# wagband_schematic_pre_route.net
KiCad netlist of a schematic drawn in EAGLE
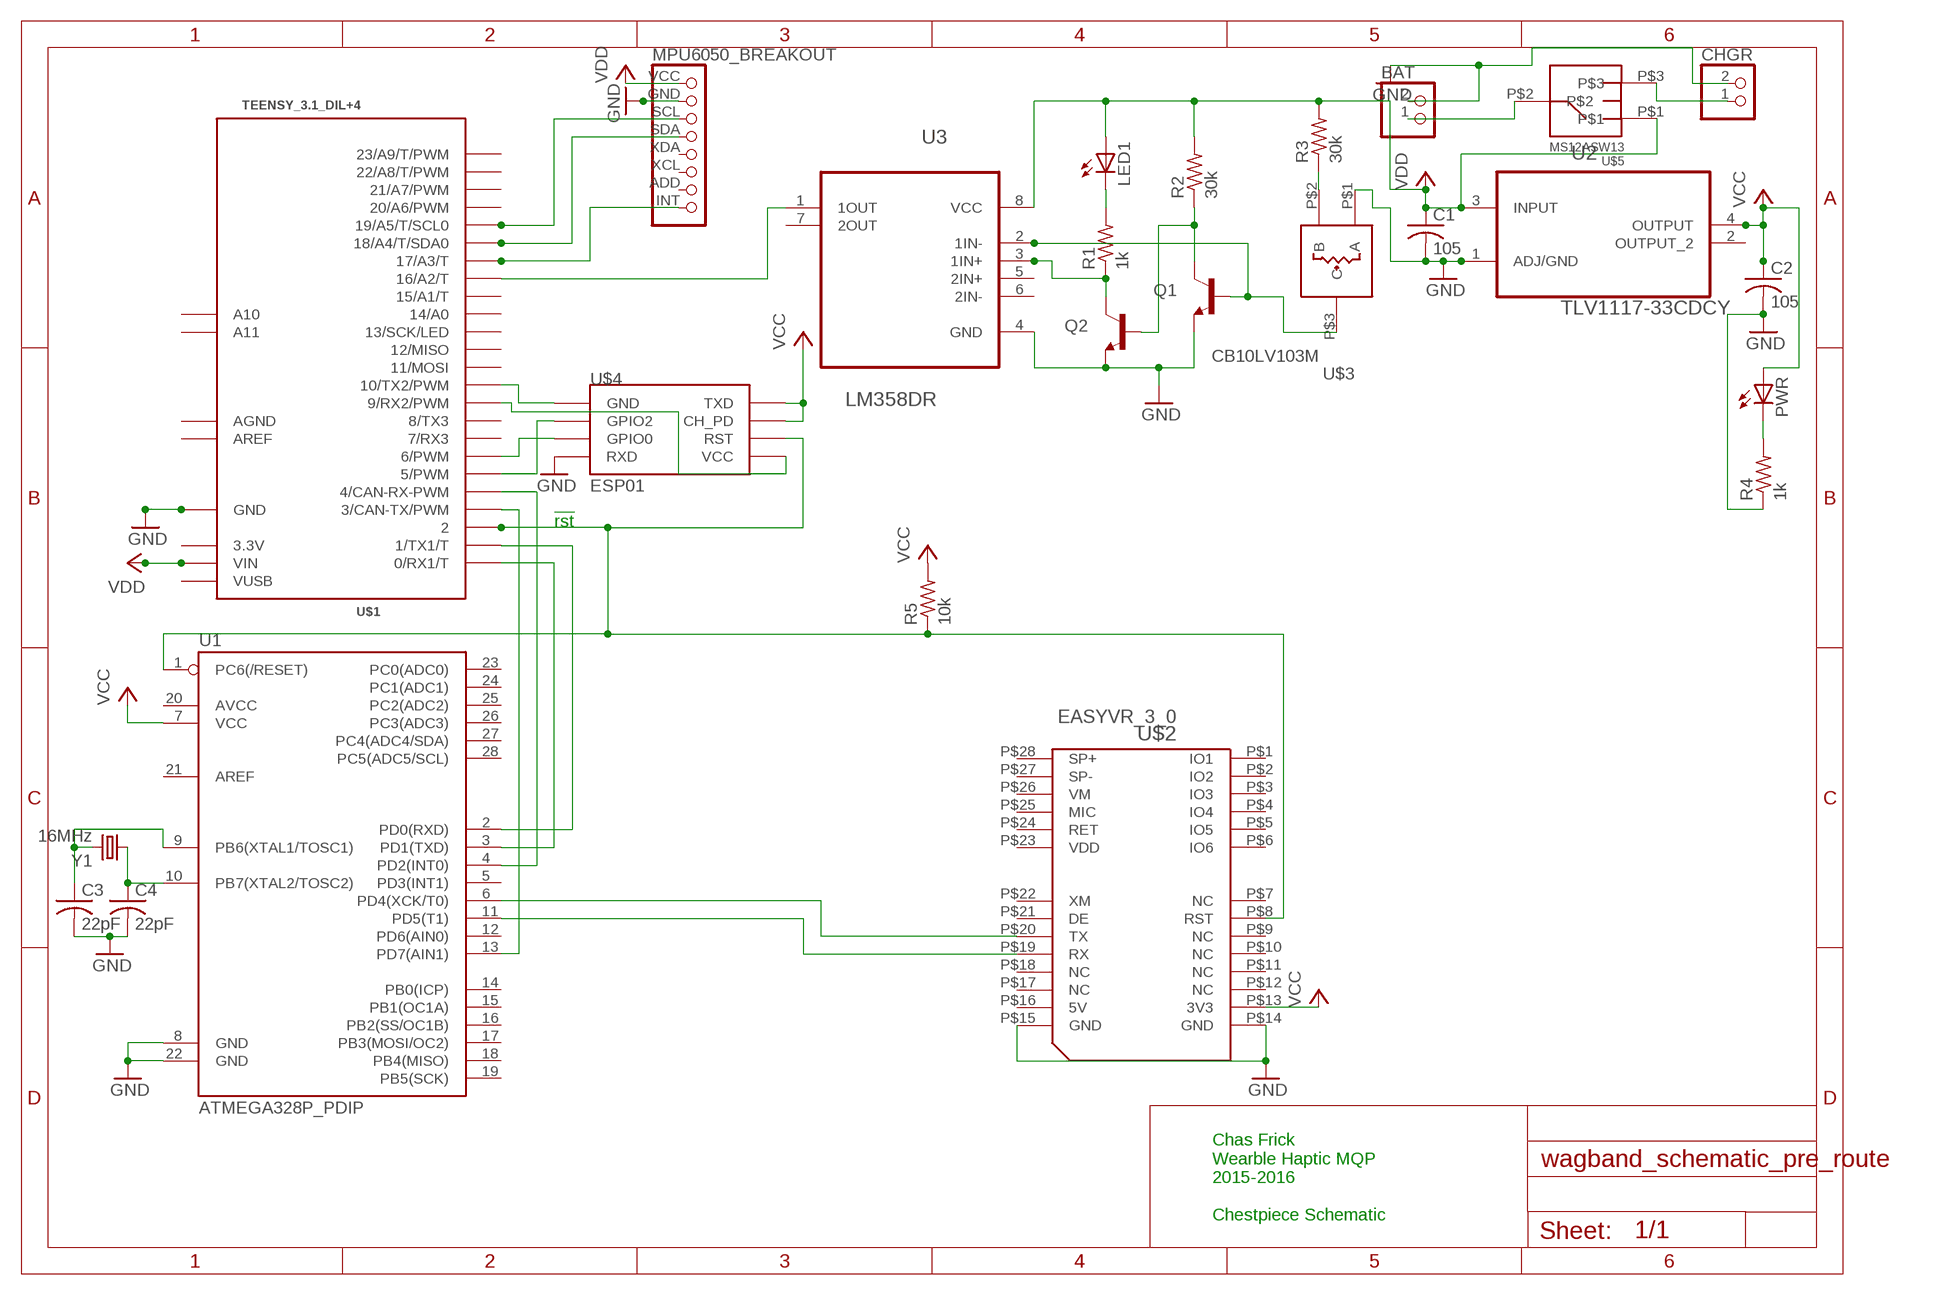
[diagram p0: schematic, sheet 1]

(export (version "E")
  (design (tool "Eeschema 10.0.6"))
  (components
    (comp (ref "BAT")
      (value "JST_2PIN-THM-RA")
      (footprint "eagle-import:JST-PH-2-THM-RA")
      (libsource (lib "eagle-import") (part "JST_2PIN-THM-RA"))
    )
    (comp (ref "C1")
      (value "105")
      (footprint "eagle-import:C0805K")
      (libsource (lib "eagle-import") (part "resistor_C-USC0805K"))
    )
    (comp (ref "C2")
      (value "105")
      (footprint "eagle-import:C0805K")
      (libsource (lib "eagle-import") (part "resistor_C-USC0805K"))
    )
    (comp (ref "C3")
      (value "22pF")
      (footprint "eagle-import:C1206K")
      (libsource (lib "eagle-import") (part "C-USC1206K"))
    )
    (comp (ref "C4")
      (value "22pF")
      (footprint "eagle-import:C1206K")
      (libsource (lib "eagle-import") (part "C-USC1206K"))
    )
    (comp (ref "CHGR")
      (value "JST_2PIN-THM-RA")
      (footprint "eagle-import:JST-PH-2-THM-RA")
      (libsource (lib "eagle-import") (part "JST_2PIN-THM-RA"))
    )
    (comp (ref "LED1")
      (value "LED5MM")
      (footprint "eagle-import:LED5MM")
      (libsource (lib "eagle-import") (part "LED5MM"))
    )
    (comp (ref "MPU6050_BREAKOUT")
      (value "MPU6050_BREAKOUT")
      (footprint "eagle-import:MPU6050")
      (libsource (lib "eagle-import") (part "MPU6050_BREAKOUT"))
    )
    (comp (ref "PWR")
      (value "LED5MM")
      (footprint "eagle-import:LED5MM")
      (libsource (lib "eagle-import") (part "LED5MM"))
    )
    (comp (ref "Q1")
      (value "TRANSISTOR_NPNMMBT3904")
      (footprint "eagle-import:SOT-23")
      (libsource (lib "eagle-import") (part "TRANSISTOR_NPNMMBT3904"))
    )
    (comp (ref "Q2")
      (value "TRANSISTOR_NPNMMBT3904")
      (footprint "eagle-import:SOT-23")
      (libsource (lib "eagle-import") (part "TRANSISTOR_NPNMMBT3904"))
    )
    (comp (ref "R1")
      (value "1k")
      (footprint "eagle-import:R1206")
      (libsource (lib "eagle-import") (part "R-US_R1206"))
    )
    (comp (ref "R2")
      (value "30k")
      (footprint "eagle-import:R1206")
      (libsource (lib "eagle-import") (part "R-US_R1206"))
    )
    (comp (ref "R3")
      (value "30k")
      (footprint "eagle-import:R1206")
      (libsource (lib "eagle-import") (part "R-US_R1206"))
    )
    (comp (ref "R4")
      (value "1k")
      (footprint "eagle-import:R1206")
      (libsource (lib "eagle-import") (part "R-US_R1206"))
    )
    (comp (ref "R5")
      (value "10k")
      (footprint "eagle-import:R1206")
      (libsource (lib "eagle-import") (part "R-US_R1206"))
    )
    (comp (ref "U$1")
      (value "TEENSY_3.1_DIL+4")
      (footprint "eagle-import:TEENSY3-DIL+4")
      (libsource (lib "eagle-import") (part "TEENSY_3.1_DIL+4"))
    )
    (comp (ref "U$2")
      (value "EASYVR_3_0")
      (footprint "eagle-import:EASYVR_3_0")
      (libsource (lib "eagle-import") (part "EASYVR_3_0"))
    )
    (comp (ref "U$3")
      (value "CB10LV103M")
      (footprint "eagle-import:CB10")
      (libsource (lib "eagle-import") (part "CB10LV103M"))
    )
    (comp (ref "U$4")
      (value "ESP01")
      (footprint "eagle-import:ESP01")
      (libsource (lib "eagle-import") (part "ESP01"))
    )
    (comp (ref "U$5")
      (value "MS12ASW13")
      (footprint "eagle-import:SPDT")
      (libsource (lib "eagle-import") (part "MS12ASW13"))
    )
    (comp (ref "U1")
      (value "ATMEGA328P_PDIP")
      (footprint "eagle-import:DIL28-3")
      (libsource (lib "eagle-import") (part "ATMEGA328P_PDIP"))
    )
    (comp (ref "U2")
      (value "TLV1117-33CDCY")
      (footprint "eagle-import:SOT230P700X180-4N")
      (libsource (lib "eagle-import") (part "TLV1117-33CDCY"))
    )
    (comp (ref "U3")
      (value "LM358DR")
      (footprint "eagle-import:SOIC127P600X175-8N")
      (libsource (lib "eagle-import") (part "LM358DR"))
    )
    (comp (ref "Y1")
      (value "16MHz")
      (footprint "eagle-import:HC49UP")
      (libsource (lib "eagle-import") (part "CRYSTALSMD"))
    )
  )
  (nets
    (net (code "1") (name "/3.3V") (class "Default")
      (node (ref "U$1") (pin "3.3V") (pinfunction "3.3V_3.3V") (pintype "power_in"))
    )
    (net (code "2") (name "/AGND") (class "Default")
      (node (ref "U$1") (pin "AGND") (pinfunction "AGND_AGND") (pintype "power_in"))
    )
    (net (code "3") (name "/AREF") (class "Default")
      (node (ref "U$1") (pin "AREF") (pinfunction "AREF_AREF") (pintype "power_in"))
    )
    (net (code "4") (name "/VUSB") (class "Default")
      (node (ref "U$1") (pin "VUSB") (pinfunction "VUSB_VUSB") (pintype "power_in"))
    )
    (net (code "5") (name "GND") (class "Default")
      (node (ref "BAT") (pin "2") (pinfunction "1_2") (pintype "passive"))
      (node (ref "C1") (pin "2") (pinfunction "2_2") (pintype "passive"))
      (node (ref "C2") (pin "2") (pinfunction "2_2") (pintype "passive"))
      (node (ref "C3") (pin "2") (pinfunction "2_2") (pintype "passive"))
      (node (ref "C4") (pin "2") (pinfunction "2_2") (pintype "passive"))
      (node (ref "CHGR") (pin "2") (pinfunction "1_2") (pintype "passive"))
      (node (ref "MPU6050_BREAKOUT") (pin "GND") (pinfunction "GND_GND") (pintype "passive"))
      (node (ref "Q1") (pin "2") (pinfunction "E_2") (pintype "passive"))
      (node (ref "Q2") (pin "2") (pinfunction "E_2") (pintype "passive"))
      (node (ref "R4") (pin "1") (pinfunction "1_1") (pintype "passive"))
      (node (ref "U$1") (pin "GND") (pinfunction "GND_GND") (pintype "power_in"))
      (node (ref "U$2") (pin "P$14") (pinfunction "GND_P$14") (pintype "power_in"))
      (node (ref "U$2") (pin "P$15") (pinfunction "GND_P$15") (pintype "power_in"))
      (node (ref "U$3") (pin "P$1") (pinfunction "A_P$1") (pintype "bidirectional"))
      (node (ref "U$4") (pin "RX") (pinfunction "RXD_RX") (pintype "bidirectional"))
      (node (ref "U1") (pin "22") (pinfunction "GND_22") (pintype "bidirectional"))
      (node (ref "U1") (pin "8") (pinfunction "GND_8") (pintype "bidirectional"))
      (node (ref "U2") (pin "1") (pinfunction "ADJ/GND_1") (pintype "input"))
      (node (ref "U3") (pin "4") (pinfunction "GND_4") (pintype "passive"))
    )
    (net (code "6") (name "Net-(BAT-2)") (class "Default")
      (node (ref "BAT") (pin "1") (pinfunction "2_1") (pintype "passive"))
      (node (ref "U$5") (pin "P$2") (pinfunction "P$2_P$2") (pintype "bidirectional"))
    )
    (net (code "7") (name "Net-(CHGR-2)") (class "Default")
      (node (ref "CHGR") (pin "1") (pinfunction "2_1") (pintype "passive"))
      (node (ref "U$5") (pin "P$3") (pinfunction "P$3_P$3") (pintype "bidirectional"))
    )
    (net (code "8") (name "Net-(LED1-C)") (class "Default")
      (node (ref "LED1") (pin "K") (pinfunction "C_K") (pintype "passive"))
      (node (ref "R1") (pin "2") (pinfunction "2_2") (pintype "passive"))
    )
    (net (code "9") (name "Net-(PWR-C)") (class "Default")
      (node (ref "PWR") (pin "K") (pinfunction "C_K") (pintype "passive"))
      (node (ref "R4") (pin "2") (pinfunction "2_2") (pintype "passive"))
    )
    (net (code "10") (name "Net-(Q1-B)") (class "Default")
      (node (ref "Q1") (pin "1") (pinfunction "B_1") (pintype "passive"))
      (node (ref "U$3") (pin "P$3") (pinfunction "C_P$3") (pintype "bidirectional"))
      (node (ref "U3") (pin "2") (pinfunction "1IN-_2") (pintype "input"))
    )
    (net (code "11") (name "Net-(Q1-C)") (class "Default")
      (node (ref "Q1") (pin "3") (pinfunction "C_3") (pintype "passive"))
      (node (ref "Q2") (pin "1") (pinfunction "B_1") (pintype "passive"))
      (node (ref "R2") (pin "1") (pinfunction "1_1") (pintype "passive"))
    )
    (net (code "12") (name "Net-(Q2-C)") (class "Default")
      (node (ref "Q2") (pin "3") (pinfunction "C_3") (pintype "passive"))
      (node (ref "R1") (pin "1") (pinfunction "1_1") (pintype "passive"))
      (node (ref "U3") (pin "3") (pinfunction "1IN+_3") (pintype "input"))
    )
    (net (code "13") (name "Net-(U$1-0{slash}RX1{slash}T)") (class "Default")
      (node (ref "U$1") (pin "0") (pinfunction "0/RX1/T_0") (pintype "bidirectional"))
      (node (ref "U1") (pin "3") (pinfunction "PD1(TXD)_3") (pintype "bidirectional"))
    )
    (net (code "14") (name "Net-(U$1-1{slash}TX1{slash}T)") (class "Default")
      (node (ref "U$1") (pin "1") (pinfunction "1/TX1/T_1") (pintype "bidirectional"))
      (node (ref "U1") (pin "2") (pinfunction "PD0(RXD)_2") (pintype "bidirectional"))
    )
    (net (code "15") (name "Net-(U$1-3{slash}CAN-TX{slash}PWM)") (class "Default")
      (node (ref "U$1") (pin "3") (pinfunction "3/CAN-TX/PWM_3") (pintype "bidirectional"))
      (node (ref "U1") (pin "13") (pinfunction "PD7(AIN1)_13") (pintype "bidirectional"))
    )
    (net (code "16") (name "Net-(U$1-4{slash}CAN-RX-PWM)") (class "Default")
      (node (ref "U$1") (pin "4") (pinfunction "4/CAN-RX-PWM_4") (pintype "bidirectional"))
      (node (ref "U1") (pin "4") (pinfunction "PD2(INT0)_4") (pintype "bidirectional"))
    )
    (net (code "17") (name "Net-(U$1-5{slash}PWM)") (class "Default")
      (node (ref "U$1") (pin "5") (pinfunction "5/PWM_5") (pintype "bidirectional"))
      (node (ref "U$4") (pin "GPIO2") (pinfunction "GPIO2_GPIO2") (pintype "bidirectional"))
    )
    (net (code "18") (name "Net-(U$1-6{slash}PWM)") (class "Default")
      (node (ref "U$1") (pin "6") (pinfunction "6/PWM_6") (pintype "bidirectional"))
      (node (ref "U$4") (pin "GPIO0") (pinfunction "GPIO0_GPIO0") (pintype "bidirectional"))
    )
    (net (code "19") (name "Net-(U$1-9{slash}RX2{slash}PWM)") (class "Default")
      (node (ref "U$1") (pin "9") (pinfunction "9/RX2/PWM_9") (pintype "bidirectional"))
      (node (ref "U$4") (pin "VCC") (pinfunction "VCC_VCC") (pintype "bidirectional"))
    )
    (net (code "20") (name "Net-(U$1-10{slash}TX2{slash}PWM)") (class "Default")
      (node (ref "U$1") (pin "10") (pinfunction "10/TX2/PWM_10") (pintype "bidirectional"))
      (node (ref "U$4") (pin "GND") (pinfunction "GND_GND") (pintype "bidirectional"))
    )
    (net (code "21") (name "Net-(U$1-16{slash}A2{slash}T)") (class "Default")
      (node (ref "U$1") (pin "16/A2") (pinfunction "16/A2/T_16/A2") (pintype "bidirectional"))
      (node (ref "U3") (pin "1") (pinfunction "1OUT_1") (pintype "output"))
    )
    (net (code "22") (name "Net-(U$1-17{slash}A3{slash}T)") (class "Default")
      (node (ref "MPU6050_BREAKOUT") (pin "INT") (pinfunction "INT_INT") (pintype "passive"))
      (node (ref "U$1") (pin "17/A3") (pinfunction "17/A3/T_17/A3") (pintype "bidirectional"))
    )
    (net (code "23") (name "Net-(U$1-18{slash}A4{slash}T{slash}SDA0)") (class "Default")
      (node (ref "MPU6050_BREAKOUT") (pin "SDA") (pinfunction "SDA_SDA") (pintype "passive"))
      (node (ref "U$1") (pin "18/A4") (pinfunction "18/A4/T/SDA0_18/A4") (pintype "bidirectional"))
    )
    (net (code "24") (name "Net-(U$1-19{slash}A5{slash}T{slash}SCL0)") (class "Default")
      (node (ref "MPU6050_BREAKOUT") (pin "SCL") (pinfunction "SCL_SCL") (pintype "passive"))
      (node (ref "U$1") (pin "19/A5") (pinfunction "19/A5/T/SCL0_19/A5") (pintype "bidirectional"))
    )
    (net (code "25") (name "Net-(U$2-RST)") (class "Default")
      (node (ref "R5") (pin "1") (pinfunction "1_1") (pintype "passive"))
      (node (ref "U$1") (pin "2") (pinfunction "2_2") (pintype "bidirectional"))
      (node (ref "U$2") (pin "P$8") (pinfunction "RST_P$8") (pintype "input"))
      (node (ref "U$4") (pin "RST") (pinfunction "RST_RST") (pintype "bidirectional"))
      (node (ref "U1") (pin "1") (pinfunction "PC6(/RESET)_1") (pintype "bidirectional"))
    )
    (net (code "26") (name "Net-(U$2-RX)") (class "Default")
      (node (ref "U$2") (pin "P$19") (pinfunction "RX_P$19") (pintype "input"))
      (node (ref "U1") (pin "11") (pinfunction "PD5(T1)_11") (pintype "bidirectional"))
    )
    (net (code "27") (name "Net-(U$2-TX)") (class "Default")
      (node (ref "U$2") (pin "P$20") (pinfunction "TX_P$20") (pintype "output"))
      (node (ref "U1") (pin "6") (pinfunction "PD4(XCK/T0)_6") (pintype "bidirectional"))
    )
    (net (code "28") (name "Net-(U$3-B)") (class "Default")
      (node (ref "R3") (pin "1") (pinfunction "1_1") (pintype "passive"))
      (node (ref "U$3") (pin "P$2") (pinfunction "B_P$2") (pintype "bidirectional"))
    )
    (net (code "29") (name "Net-(U1-PB6(XTAL1{slash}TOSC1))") (class "Default")
      (node (ref "C3") (pin "1") (pinfunction "1_1") (pintype "passive"))
      (node (ref "U1") (pin "9") (pinfunction "PB6(XTAL1/TOSC1)_9") (pintype "bidirectional"))
      (node (ref "Y1") (pin "2") (pinfunction "2_2") (pintype "passive"))
    )
    (net (code "30") (name "Net-(U1-PB7(XTAL2{slash}TOSC2))") (class "Default")
      (node (ref "C4") (pin "1") (pinfunction "1_1") (pintype "passive"))
      (node (ref "U1") (pin "10") (pinfunction "PB7(XTAL2/TOSC2)_10") (pintype "bidirectional"))
      (node (ref "Y1") (pin "1") (pinfunction "1_1") (pintype "passive"))
    )
    (net (code "31") (name "VCC") (class "Default")
      (node (ref "C1") (pin "1") (pinfunction "1_1") (pintype "passive"))
      (node (ref "C2") (pin "1") (pinfunction "1_1") (pintype "passive"))
      (node (ref "LED1") (pin "A") (pinfunction "A_A") (pintype "passive"))
      (node (ref "MPU6050_BREAKOUT") (pin "VCC") (pinfunction "VCC_VCC") (pintype "passive"))
      (node (ref "PWR") (pin "A") (pinfunction "A_A") (pintype "passive"))
      (node (ref "R2") (pin "2") (pinfunction "2_2") (pintype "passive"))
      (node (ref "R3") (pin "2") (pinfunction "2_2") (pintype "passive"))
      (node (ref "R5") (pin "2") (pinfunction "2_2") (pintype "passive"))
      (node (ref "U$1") (pin "VIN") (pinfunction "VIN_VIN") (pintype "power_in"))
      (node (ref "U$2") (pin "P$13") (pinfunction "3V3_P$13") (pintype "power_in"))
      (node (ref "U$4") (pin "CH_PD") (pinfunction "CH_PD_CH_PD") (pintype "bidirectional"))
      (node (ref "U$4") (pin "TX") (pinfunction "TXD_TX") (pintype "bidirectional"))
      (node (ref "U$5") (pin "P$1") (pinfunction "P$1_P$1") (pintype "bidirectional"))
      (node (ref "U1") (pin "7") (pinfunction "VCC_7") (pintype "bidirectional"))
      (node (ref "U2") (pin "3") (pinfunction "INPUT_3") (pintype "input"))
      (node (ref "U2") (pin "4") (pinfunction "OUTPUT_4") (pintype "output"))
      (node (ref "U3") (pin "8") (pinfunction "VCC_8") (pintype "power_in"))
    )
    (net (code "32") (name "unconnected-(MPU6050_BREAKOUT-PadADD)") (class "Default")
      (node (ref "MPU6050_BREAKOUT") (pin "ADD") (pinfunction "ADD_ADD") (pintype "passive"))
    )
    (net (code "33") (name "unconnected-(MPU6050_BREAKOUT-PadXCL)") (class "Default")
      (node (ref "MPU6050_BREAKOUT") (pin "XCL") (pinfunction "XCL_XCL") (pintype "passive"))
    )
    (net (code "34") (name "unconnected-(MPU6050_BREAKOUT-PadXDA)") (class "Default")
      (node (ref "MPU6050_BREAKOUT") (pin "XDA") (pinfunction "XDA_XDA") (pintype "passive"))
    )
    (net (code "35") (name "unconnected-(U$1-7{slash}RX3-Pad7)") (class "Default")
      (node (ref "U$1") (pin "7") (pinfunction "7/RX3_7") (pintype "bidirectional"))
    )
    (net (code "36") (name "unconnected-(U$1-8{slash}TX3-Pad8)") (class "Default")
      (node (ref "U$1") (pin "8") (pinfunction "8/TX3_8") (pintype "bidirectional"))
    )
    (net (code "37") (name "unconnected-(U$1-11{slash}MOSI-Pad11)") (class "Default")
      (node (ref "U$1") (pin "11") (pinfunction "11/MOSI_11") (pintype "bidirectional"))
    )
    (net (code "38") (name "unconnected-(U$1-12{slash}MISO-Pad12)") (class "Default")
      (node (ref "U$1") (pin "12") (pinfunction "12/MISO_12") (pintype "bidirectional"))
    )
    (net (code "39") (name "unconnected-(U$1-13{slash}SCK{slash}LED-Pad13)") (class "Default")
      (node (ref "U$1") (pin "13") (pinfunction "13/SCK/LED_13") (pintype "bidirectional"))
    )
    (net (code "40") (name "unconnected-(U$1-15{slash}A1{slash}T-Pad15{slash}A1)") (class "Default")
      (node (ref "U$1") (pin "15/A1") (pinfunction "15/A1/T_15/A1") (pintype "bidirectional"))
    )
    (net (code "41") (name "unconnected-(U$1-20{slash}A6{slash}PWM-Pad20{slash}A6)") (class "Default")
      (node (ref "U$1") (pin "20/A6") (pinfunction "20/A6/PWM_20/A6") (pintype "bidirectional"))
    )
    (net (code "42") (name "unconnected-(U$1-21{slash}A7{slash}PWM-Pad21{slash}A7)") (class "Default")
      (node (ref "U$1") (pin "21/A7") (pinfunction "21/A7/PWM_21/A7") (pintype "bidirectional"))
    )
    (net (code "43") (name "unconnected-(U$1-22{slash}A8{slash}T{slash}PWM-Pad22{slash}A8)") (class "Default")
      (node (ref "U$1") (pin "22/A8") (pinfunction "22/A8/T/PWM_22/A8") (pintype "bidirectional"))
    )
    (net (code "44") (name "unconnected-(U$1-23{slash}A9{slash}T{slash}PWM-Pad23{slash}A9)") (class "Default")
      (node (ref "U$1") (pin "23/A9") (pinfunction "23/A9/T/PWM_23/A9") (pintype "bidirectional"))
    )
    (net (code "45") (name "unconnected-(U$1-Pad14{slash}A0)") (class "Default")
      (node (ref "U$1") (pin "14/A0") (pinfunction "14/A0_14/A0") (pintype "bidirectional"))
    )
    (net (code "46") (name "unconnected-(U$1-PadA10)") (class "Default")
      (node (ref "U$1") (pin "A10") (pinfunction "A10_A10") (pintype "bidirectional"))
    )
    (net (code "47") (name "unconnected-(U$1-PadA11)") (class "Default")
      (node (ref "U$1") (pin "A11") (pinfunction "A11_A11") (pintype "bidirectional"))
    )
    (net (code "48") (name "unconnected-(U$2-5V-PadP$16)") (class "Default")
      (node (ref "U$2") (pin "P$16") (pinfunction "5V_P$16") (pintype "power_in"))
    )
    (net (code "49") (name "unconnected-(U$2-DE-PadP$21)") (class "Default")
      (node (ref "U$2") (pin "P$21") (pinfunction "DE_P$21") (pintype "bidirectional"))
    )
    (net (code "50") (name "unconnected-(U$2-IO1-PadP$1)") (class "Default")
      (node (ref "U$2") (pin "P$1") (pinfunction "IO1_P$1") (pintype "bidirectional"))
    )
    (net (code "51") (name "unconnected-(U$2-IO2-PadP$2)") (class "Default")
      (node (ref "U$2") (pin "P$2") (pinfunction "IO2_P$2") (pintype "bidirectional"))
    )
    (net (code "52") (name "unconnected-(U$2-IO3-PadP$3)") (class "Default")
      (node (ref "U$2") (pin "P$3") (pinfunction "IO3_P$3") (pintype "bidirectional"))
    )
    (net (code "53") (name "unconnected-(U$2-IO4-PadP$4)") (class "Default")
      (node (ref "U$2") (pin "P$4") (pinfunction "IO4_P$4") (pintype "bidirectional"))
    )
    (net (code "54") (name "unconnected-(U$2-IO5-PadP$5)") (class "Default")
      (node (ref "U$2") (pin "P$5") (pinfunction "IO5_P$5") (pintype "bidirectional"))
    )
    (net (code "55") (name "unconnected-(U$2-IO6-PadP$6)") (class "Default")
      (node (ref "U$2") (pin "P$6") (pinfunction "IO6_P$6") (pintype "bidirectional"))
    )
    (net (code "56") (name "unconnected-(U$2-MIC-PadP$25)") (class "Default")
      (node (ref "U$2") (pin "P$25") (pinfunction "MIC_P$25") (pintype "bidirectional"))
    )
    (net (code "57") (name "unconnected-(U$2-NC-PadP$7)") (class "Default")
      (node (ref "U$2") (pin "P$7") (pinfunction "NC_P$7") (pintype "no_connect"))
    )
    (net (code "58") (name "unconnected-(U$2-NC-PadP$9)") (class "Default")
      (node (ref "U$2") (pin "P$9") (pinfunction "NC_P$9") (pintype "no_connect"))
    )
    (net (code "59") (name "unconnected-(U$2-NC-PadP$10)") (class "Default")
      (node (ref "U$2") (pin "P$10") (pinfunction "NC_P$10") (pintype "no_connect"))
    )
    (net (code "60") (name "unconnected-(U$2-NC-PadP$11)") (class "Default")
      (node (ref "U$2") (pin "P$11") (pinfunction "NC_P$11") (pintype "no_connect"))
    )
    (net (code "61") (name "unconnected-(U$2-NC-PadP$12)") (class "Default")
      (node (ref "U$2") (pin "P$12") (pinfunction "NC_P$12") (pintype "no_connect"))
    )
    (net (code "62") (name "unconnected-(U$2-NC-PadP$17)") (class "Default")
      (node (ref "U$2") (pin "P$17") (pinfunction "NC_P$17") (pintype "no_connect"))
    )
    (net (code "63") (name "unconnected-(U$2-NC-PadP$18)") (class "Default")
      (node (ref "U$2") (pin "P$18") (pinfunction "NC_P$18") (pintype "no_connect"))
    )
    (net (code "64") (name "unconnected-(U$2-RET-PadP$24)") (class "Default")
      (node (ref "U$2") (pin "P$24") (pinfunction "RET_P$24") (pintype "bidirectional"))
    )
    (net (code "65") (name "unconnected-(U$2-SP+-PadP$28)") (class "Default")
      (node (ref "U$2") (pin "P$28") (pinfunction "SP+_P$28") (pintype "bidirectional"))
    )
    (net (code "66") (name "unconnected-(U$2-SP--PadP$27)") (class "Default")
      (node (ref "U$2") (pin "P$27") (pinfunction "SP-_P$27") (pintype "bidirectional"))
    )
    (net (code "67") (name "unconnected-(U$2-VDD-PadP$23)") (class "Default")
      (node (ref "U$2") (pin "P$23") (pinfunction "VDD_P$23") (pintype "power_in"))
    )
    (net (code "68") (name "unconnected-(U$2-VM-PadP$26)") (class "Default")
      (node (ref "U$2") (pin "P$26") (pinfunction "VM_P$26") (pintype "bidirectional"))
    )
    (net (code "69") (name "unconnected-(U$2-XM-PadP$22)") (class "Default")
      (node (ref "U$2") (pin "P$22") (pinfunction "XM_P$22") (pintype "bidirectional"))
    )
    (net (code "70") (name "unconnected-(U1-AREF-Pad21)") (class "Default")
      (node (ref "U1") (pin "21") (pinfunction "AREF_21") (pintype "bidirectional"))
    )
    (net (code "71") (name "unconnected-(U1-AVCC-Pad20)") (class "Default")
      (node (ref "U1") (pin "20") (pinfunction "AVCC_20") (pintype "bidirectional"))
    )
    (net (code "72") (name "unconnected-(U1-PB0(ICP)-Pad14)") (class "Default")
      (node (ref "U1") (pin "14") (pinfunction "PB0(ICP)_14") (pintype "bidirectional"))
    )
    (net (code "73") (name "unconnected-(U1-PB1(OC1A)-Pad15)") (class "Default")
      (node (ref "U1") (pin "15") (pinfunction "PB1(OC1A)_15") (pintype "bidirectional"))
    )
    (net (code "74") (name "unconnected-(U1-PB2(SS{slash}OC1B)-Pad16)") (class "Default")
      (node (ref "U1") (pin "16") (pinfunction "PB2(SS/OC1B)_16") (pintype "bidirectional"))
    )
    (net (code "75") (name "unconnected-(U1-PB3(MOSI{slash}OC2)-Pad17)") (class "Default")
      (node (ref "U1") (pin "17") (pinfunction "PB3(MOSI/OC2)_17") (pintype "bidirectional"))
    )
    (net (code "76") (name "unconnected-(U1-PB4(MISO)-Pad18)") (class "Default")
      (node (ref "U1") (pin "18") (pinfunction "PB4(MISO)_18") (pintype "bidirectional"))
    )
    (net (code "77") (name "unconnected-(U1-PB5(SCK)-Pad19)") (class "Default")
      (node (ref "U1") (pin "19") (pinfunction "PB5(SCK)_19") (pintype "bidirectional"))
    )
    (net (code "78") (name "unconnected-(U1-PC0(ADC0)-Pad23)") (class "Default")
      (node (ref "U1") (pin "23") (pinfunction "PC0(ADC0)_23") (pintype "bidirectional"))
    )
    (net (code "79") (name "unconnected-(U1-PC1(ADC1)-Pad24)") (class "Default")
      (node (ref "U1") (pin "24") (pinfunction "PC1(ADC1)_24") (pintype "bidirectional"))
    )
    (net (code "80") (name "unconnected-(U1-PC2(ADC2)-Pad25)") (class "Default")
      (node (ref "U1") (pin "25") (pinfunction "PC2(ADC2)_25") (pintype "bidirectional"))
    )
    (net (code "81") (name "unconnected-(U1-PC3(ADC3)-Pad26)") (class "Default")
      (node (ref "U1") (pin "26") (pinfunction "PC3(ADC3)_26") (pintype "bidirectional"))
    )
    (net (code "82") (name "unconnected-(U1-PC4(ADC4{slash}SDA)-Pad27)") (class "Default")
      (node (ref "U1") (pin "27") (pinfunction "PC4(ADC4/SDA)_27") (pintype "bidirectional"))
    )
    (net (code "83") (name "unconnected-(U1-PC5(ADC5{slash}SCL)-Pad28)") (class "Default")
      (node (ref "U1") (pin "28") (pinfunction "PC5(ADC5/SCL)_28") (pintype "bidirectional"))
    )
    (net (code "84") (name "unconnected-(U1-PD3(INT1)-Pad5)") (class "Default")
      (node (ref "U1") (pin "5") (pinfunction "PD3(INT1)_5") (pintype "bidirectional"))
    )
    (net (code "85") (name "unconnected-(U1-PD6(AIN0)-Pad12)") (class "Default")
      (node (ref "U1") (pin "12") (pinfunction "PD6(AIN0)_12") (pintype "bidirectional"))
    )
    (net (code "86") (name "unconnected-(U2-OUTPUT_2-Pad2)") (class "Default")
      (node (ref "U2") (pin "2") (pinfunction "OUTPUT_2_2") (pintype "output"))
    )
    (net (code "87") (name "unconnected-(U3-2IN+-Pad5)") (class "Default")
      (node (ref "U3") (pin "5") (pinfunction "2IN+_5") (pintype "input"))
    )
    (net (code "88") (name "unconnected-(U3-2IN--Pad6)") (class "Default")
      (node (ref "U3") (pin "6") (pinfunction "2IN-_6") (pintype "input"))
    )
    (net (code "89") (name "unconnected-(U3-2OUT-Pad7)") (class "Default")
      (node (ref "U3") (pin "7") (pinfunction "2OUT_7") (pintype "output"))
    )
  )
)
